# design.net
KiCad netlist of a schematic drawn in Altium Designer
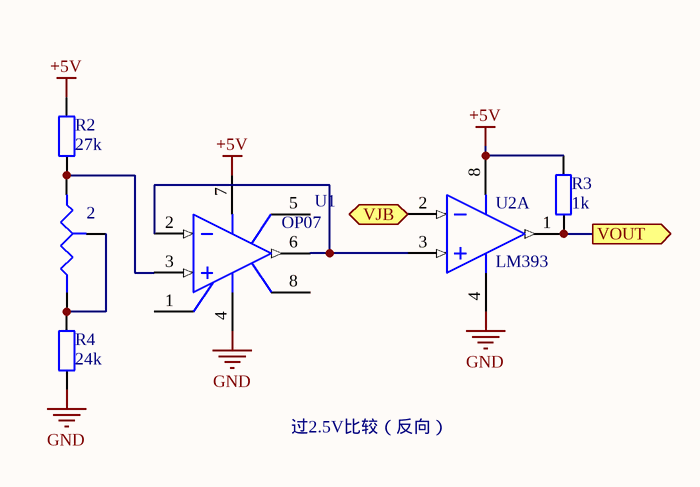
[diagram p0: 比较器.SchDoc]

(export (version "E")
  (design (tool "Eeschema 10.0.6"))
  (components
    (comp (ref "2") (value "滑阻") (footprint "三脚滑阻") (libsource (lib "自制库（原理图文件）") (part "滑阻")))
    (comp (ref "R2")
      (value "27k")
      (footprint "AXIAL-0.4")
      (description "Resistor")
      (fields (field (name "Comment") "Res2") (field (name "PUBLISHER") "Altium Limited"))
      (libsource (lib "Miscellaneous Devices") (part "Res2"))
    )
    (comp (ref "R3")
      (value "1k")
      (footprint "AXIAL-0.4")
      (description "Resistor")
      (fields (field (name "Comment") "Res2") (field (name "PUBLISHER") "Altium Limited"))
      (libsource (lib "Miscellaneous Devices") (part "Res2"))
    )
    (comp (ref "R4")
      (value "24k")
      (footprint "AXIAL-0.4")
      (description "Resistor")
      (fields (field (name "Comment") "Res2") (field (name "PUBLISHER") "Altium Limited"))
      (libsource (lib "Miscellaneous Devices") (part "Res2"))
    )
    (comp (ref "U1")
      (value "OP07")
      (footprint "N-8_A")
      (description "Ultra-Low Offset Voltage Operational Amplifier")
      (fields (field (name "PUBLISHER") "Altium Limited"))
      (libsource (lib "AD Operational Amplifier") (part "ADOP07CN"))
    )
    (comp (ref "U2")
      (value "LM393")
      (footprint "626-05")
      (description "Dual Comparator")
      (fields (field (name "PUBLISHER") "Altium Limited"))
      (libsource (lib "Motorola Analog Comparator") (part "LM393AN"))
    )
  )
  (nets
    (net (code "1") (name "+5V") (class "Default")
      (node (ref "R2") (pin "2") (pinfunction "2_2") (pintype "passive"))
      (node (ref "R3") (pin "2") (pinfunction "2_2") (pintype "passive"))
      (node (ref "U1") (pin "7") (pinfunction "V+_7") (pintype "power_in"))
      (node (ref "U2") (pin "8") (pinfunction "V+_8") (pintype "power_in"))
    )
    (net (code "2") (name "/VJB") (class "Default")
      (node (ref "U2") (pin "2") (pinfunction "IN-_2") (pintype "input"))
    )
    (net (code "3") (name "/VOUT") (class "Default")
      (node (ref "R3") (pin "1") (pinfunction "1_1") (pintype "passive"))
      (node (ref "U2") (pin "1") (pinfunction "OUT_1") (pintype "output"))
    )
    (net (code "4") (name "GND") (class "Default")
      (node (ref "R4") (pin "1") (pinfunction "1_1") (pintype "passive"))
      (node (ref "U1") (pin "4") (pinfunction "V-_4") (pintype "power_in"))
      (node (ref "U2") (pin "4") (pinfunction "GND_4") (pintype "power_in"))
    )
    (net (code "5") (name "Net-(2-A)") (class "Default")
      (node (ref "2") (pin "1") (pinfunction "A_1") (pintype "passive"))
      (node (ref "R2") (pin "1") (pinfunction "1_1") (pintype "passive"))
      (node (ref "U1") (pin "3") (pinfunction "IN+_3") (pintype "input"))
    )
    (net (code "6") (name "Net-(2-B)") (class "Default")
      (node (ref "2") (pin "2") (pinfunction "TAP_2") (pintype "passive"))
      (node (ref "2") (pin "3") (pinfunction "B_3") (pintype "passive"))
      (node (ref "R4") (pin "2") (pinfunction "2_2") (pintype "passive"))
    )
    (net (code "7") (name "Net-(U1-IN-)") (class "Default")
      (node (ref "U1") (pin "2") (pinfunction "IN-_2") (pintype "input"))
      (node (ref "U1") (pin "6") (pinfunction "OUT_6") (pintype "output"))
      (node (ref "U2") (pin "3") (pinfunction "IN+_3") (pintype "input"))
    )
    (net (code "8") (name "unconnected-(U1-NC-Pad5)") (class "Default")
      (node (ref "U1") (pin "5") (pinfunction "NC_5") (pintype "passive"))
    )
    (net (code "9") (name "unconnected-(U1-NULL1-Pad1)") (class "Default")
      (node (ref "U1") (pin "1") (pinfunction "NULL1_1") (pintype "passive"))
    )
    (net (code "10") (name "unconnected-(U1-NULL2-Pad8)") (class "Default")
      (node (ref "U1") (pin "8") (pinfunction "NULL2_8") (pintype "passive"))
    )
  )
)
